# ProPrj___2025-05-21.net
KiCad netlist of a schematic drawn in EasyEDA Pro
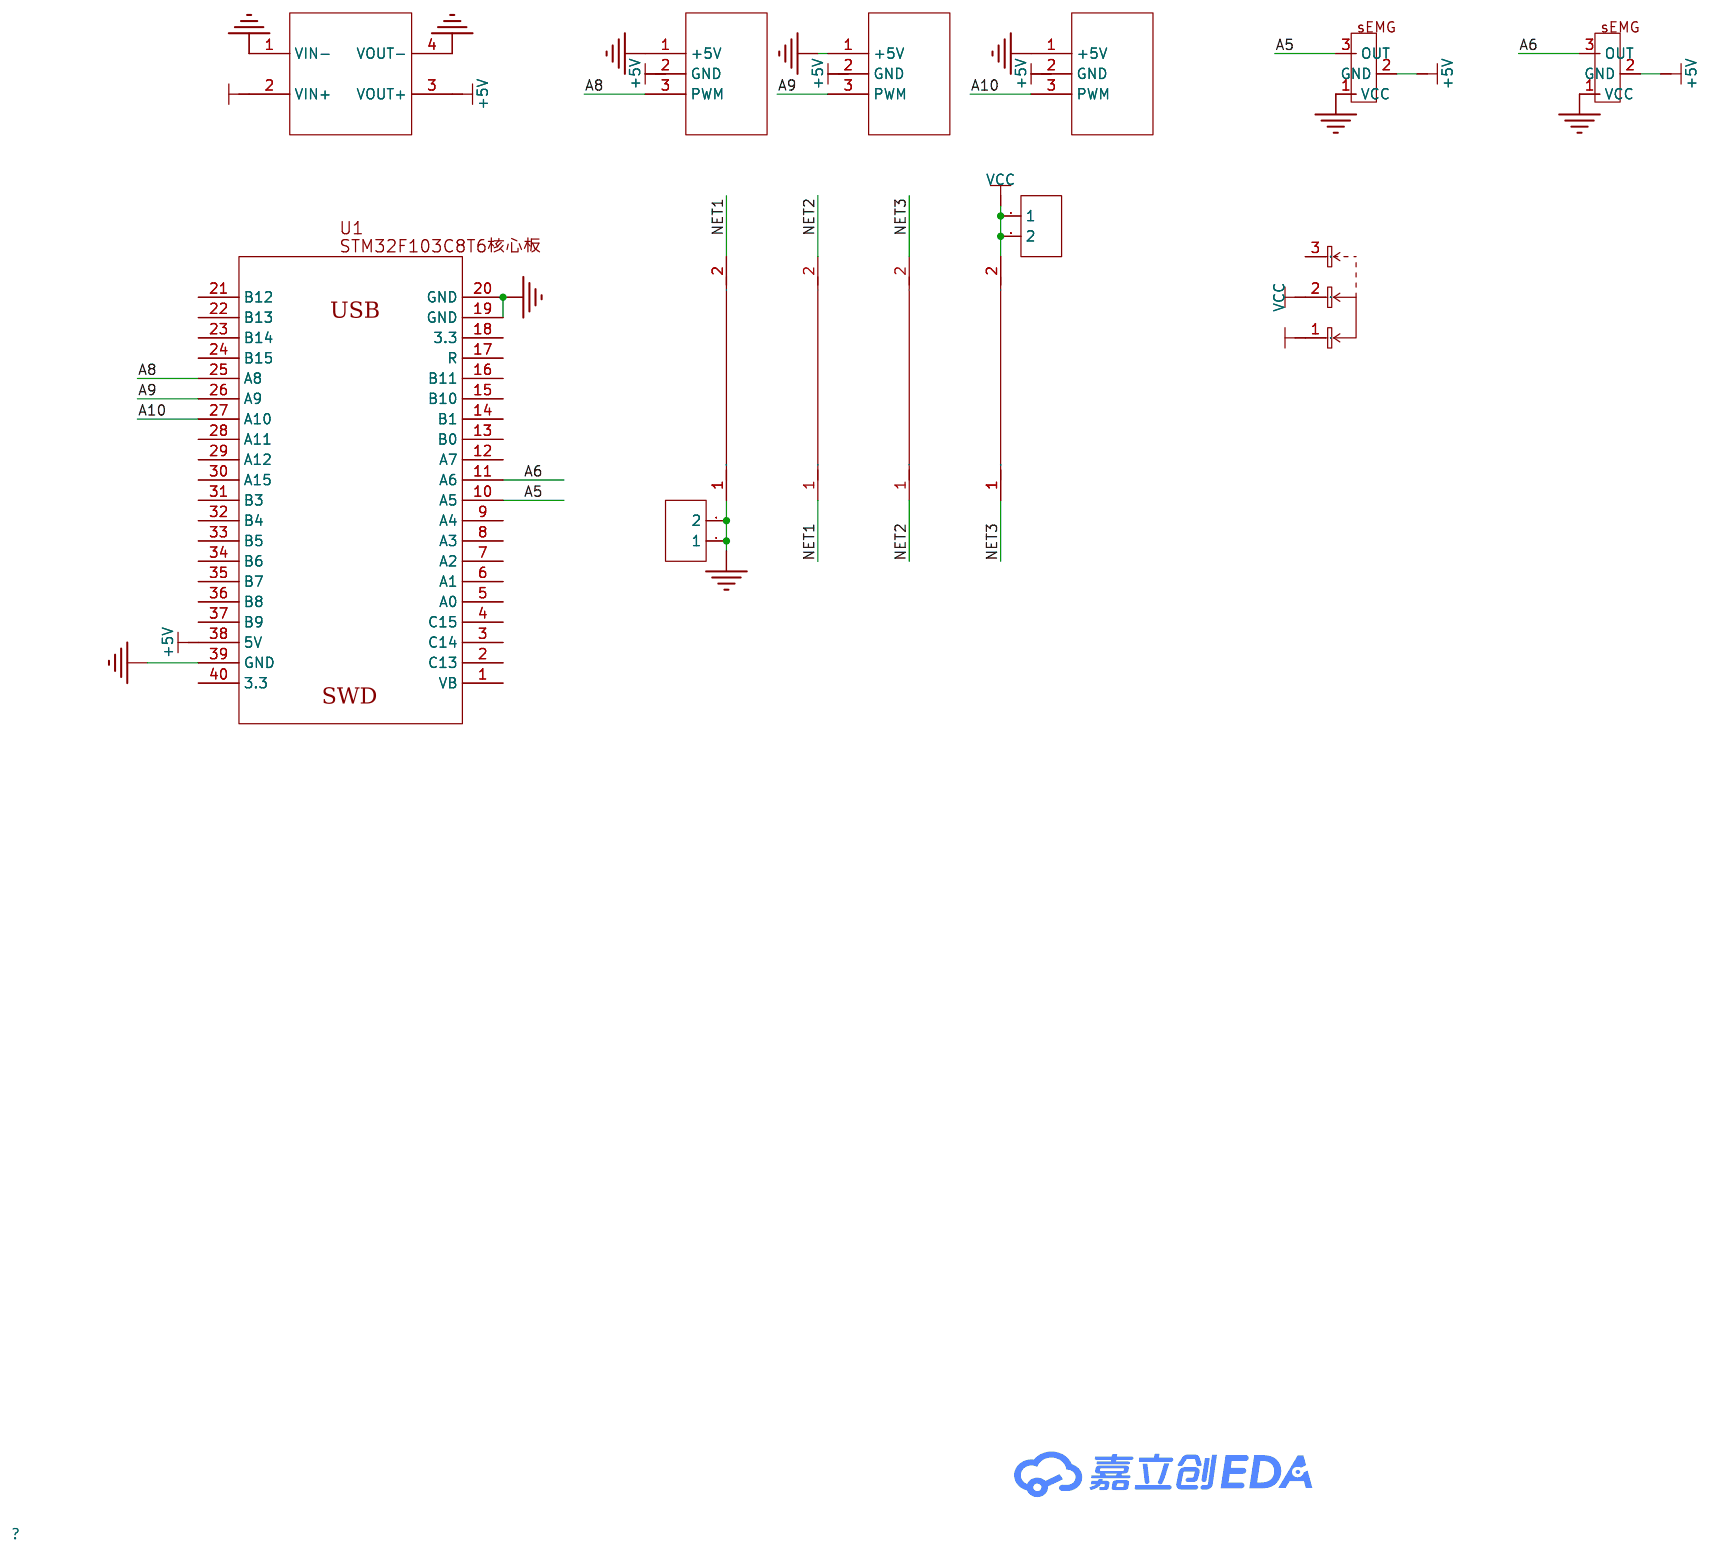
[diagram p0: schematic sheet]

(export (version "E")
  (design (tool "Eeschema 10.0.6"))
  (components
    (comp (ref "H1")
      (value "~")
      (footprint "easyedapro:HDR-TH_2P-P2.54-V-F")
      (libsource (lib "easyedapro") (part "Header-Female-2.54_1x2"))
    )
    (comp (ref "H2")
      (value "~")
      (footprint "easyedapro:HDR-TH_2P-P2.54-V-F")
      (libsource (lib "easyedapro") (part "Header-Female-2.54_1x2"))
    )
    (comp (ref "SW1")
      (value "SS-12D06L5")
      (footprint "easyedapro:SW-TH_3P-P4.70_L11.1-W12.7")
      (description "电路结构:单刀双掷;安装方式:侧插;开关颜色:黑色;额定电流(DC):3A;额定电压(DC):250V;额定电流(AC):3A;额定电压(AC):250V;机械寿命:1万次;")
      (fields (field (name "Manufacturer") "XKB Connectivity(中国星坤)"))
      (libsource (lib "easyedapro") (part "SS-12D06L5"))
    )
    (comp (ref "U1")
      (value "~")
      (footprint "easyedapro:DIP-3-2.54MM")
      (libsource (lib "easyedapro") (part "sEMG"))
    )
    (comp (ref "U3")
      (value "~")
      (footprint "easyedapro:DIP-3-2.54MM")
      (libsource (lib "easyedapro") (part "sEMG"))
    )
    (comp (ref "U4") (value "~") (footprint "easyedapro:sg90") (libsource (lib "easyedapro") (part "SG90")))
    (comp (ref "U5") (value "~") (footprint "easyedapro:sg90") (libsource (lib "easyedapro") (part "SG90")))
    (comp (ref "U6") (value "~") (footprint "easyedapro:sg90") (libsource (lib "easyedapro") (part "SG90")))
    (comp (ref "U7")
      (value "~")
      (footprint "easyedapro:STM32F103C8T6核心板")
      (libsource (lib "easyedapro") (part "STM32F103核心板"))
    )
    (comp (ref "U8")
      (value "~")
      (footprint "easyedapro:MP1584EN模块_邮票孔")
      (description "MP1584END电源模块")
      (libsource (lib "easyedapro") (part "MP1584EN模块"))
    )
    (comp (ref "U10")
      (value "~")
      (footprint "easyedapro:bat-th_cr2032")
      (libsource (lib "easyedapro") (part "CR2032 (卧式焊脚)20-6*9"))
    )
    (comp (ref "U11")
      (value "~")
      (footprint "easyedapro:bat-th_cr2032")
      (libsource (lib "easyedapro") (part "CR2032 (卧式焊脚)20-6*9"))
    )
    (comp (ref "U12")
      (value "~")
      (footprint "easyedapro:bat-th_cr2032")
      (libsource (lib "easyedapro") (part "CR2032 (卧式焊脚)20-6*9"))
    )
    (comp (ref "U13")
      (value "~")
      (footprint "easyedapro:bat-th_cr2032")
      (libsource (lib "easyedapro") (part "CR2032 (卧式焊脚)20-6*9"))
    )
  )
  (nets
    (net (code "1") (name "+5V") (class "Default")
      (node (ref "U1") (pin "2") (pinfunction "GND_2") (pintype "input"))
      (node (ref "U3") (pin "2") (pinfunction "GND_2") (pintype "input"))
      (node (ref "U4") (pin "2") (pinfunction "GND_2") (pintype "input"))
      (node (ref "U5") (pin "2") (pinfunction "GND_2") (pintype "input"))
      (node (ref "U6") (pin "2") (pinfunction "GND_2") (pintype "input"))
      (node (ref "U7") (pin "38") (pinfunction "5V_38") (pintype "input"))
      (node (ref "U8") (pin "3") (pinfunction "VOUT+_3") (pintype "input"))
    )
    (net (code "2") (name "+12V") (class "Default")
      (node (ref "SW1") (pin "1") (pinfunction "1_1") (pintype "unspecified"))
      (node (ref "U8") (pin "2") (pinfunction "VIN+_2") (pintype "input"))
    )
    (net (code "3") (name "/A5") (class "Default")
      (node (ref "U3") (pin "3") (pinfunction "OUT_3") (pintype "input"))
      (node (ref "U7") (pin "10") (pinfunction "A5_10") (pintype "input"))
    )
    (net (code "4") (name "/A6") (class "Default")
      (node (ref "U1") (pin "3") (pinfunction "OUT_3") (pintype "input"))
      (node (ref "U7") (pin "11") (pinfunction "A6_11") (pintype "input"))
    )
    (net (code "5") (name "/A8") (class "Default")
      (node (ref "U4") (pin "3") (pinfunction "PWM_3") (pintype "input"))
      (node (ref "U7") (pin "25") (pinfunction "A8_25") (pintype "input"))
    )
    (net (code "6") (name "/A9") (class "Default")
      (node (ref "U5") (pin "3") (pinfunction "PWM_3") (pintype "input"))
      (node (ref "U7") (pin "26") (pinfunction "A9_26") (pintype "input"))
    )
    (net (code "7") (name "/A10") (class "Default")
      (node (ref "U6") (pin "3") (pinfunction "PWM_3") (pintype "input"))
      (node (ref "U7") (pin "27") (pinfunction "A10_27") (pintype "input"))
    )
    (net (code "8") (name "/NET1") (class "Default")
      (node (ref "U10") (pin "2") (pinfunction "-_2") (pintype "input"))
      (node (ref "U11") (pin "1") (pinfunction "+_1") (pintype "input"))
    )
    (net (code "9") (name "/NET2") (class "Default")
      (node (ref "U11") (pin "2") (pinfunction "-_2") (pintype "input"))
      (node (ref "U12") (pin "1") (pinfunction "+_1") (pintype "input"))
    )
    (net (code "10") (name "/NET3") (class "Default")
      (node (ref "U12") (pin "2") (pinfunction "-_2") (pintype "input"))
      (node (ref "U13") (pin "1") (pinfunction "+_1") (pintype "input"))
    )
    (net (code "11") (name "GND") (class "Default")
      (node (ref "H2") (pin "1") (pinfunction "1_1") (pintype "input"))
      (node (ref "H2") (pin "2") (pinfunction "2_2") (pintype "input"))
      (node (ref "U1") (pin "1") (pinfunction "VCC_1") (pintype "input"))
      (node (ref "U10") (pin "1") (pinfunction "+_1") (pintype "input"))
      (node (ref "U3") (pin "1") (pinfunction "VCC_1") (pintype "input"))
      (node (ref "U4") (pin "1") (pinfunction "+5V_1") (pintype "input"))
      (node (ref "U5") (pin "1") (pinfunction "+5V_1") (pintype "input"))
      (node (ref "U6") (pin "1") (pinfunction "+5V_1") (pintype "input"))
      (node (ref "U7") (pin "19") (pinfunction "GND_19") (pintype "input"))
      (node (ref "U7") (pin "20") (pinfunction "GND_20") (pintype "input"))
      (node (ref "U7") (pin "39") (pinfunction "GND_39") (pintype "input"))
      (node (ref "U8") (pin "1") (pinfunction "VIN-_1") (pintype "input"))
      (node (ref "U8") (pin "4") (pinfunction "VOUT-_4") (pintype "input"))
    )
    (net (code "12") (name "VCC") (class "Default")
      (node (ref "H1") (pin "1") (pinfunction "1_1") (pintype "input"))
      (node (ref "H1") (pin "2") (pinfunction "2_2") (pintype "input"))
      (node (ref "SW1") (pin "2") (pinfunction "2_2") (pintype "unspecified"))
      (node (ref "U13") (pin "2") (pinfunction "-_2") (pintype "input"))
    )
    (net (code "13") (name "unconnected-(SW1-Pad3)") (class "Default")
      (node (ref "SW1") (pin "3") (pinfunction "3_3") (pintype "unspecified"))
    )
    (net (code "14") (name "unconnected-(U7-3.3-Pad18)") (class "Default")
      (node (ref "U7") (pin "18") (pinfunction "3.3_18") (pintype "input"))
    )
    (net (code "15") (name "unconnected-(U7-3.3-Pad40)") (class "Default")
      (node (ref "U7") (pin "40") (pinfunction "3.3_40") (pintype "input"))
    )
    (net (code "16") (name "unconnected-(U7-A0-Pad5)") (class "Default")
      (node (ref "U7") (pin "5") (pinfunction "A0_5") (pintype "input"))
    )
    (net (code "17") (name "unconnected-(U7-A1-Pad6)") (class "Default")
      (node (ref "U7") (pin "6") (pinfunction "A1_6") (pintype "input"))
    )
    (net (code "18") (name "unconnected-(U7-A2-Pad7)") (class "Default")
      (node (ref "U7") (pin "7") (pinfunction "A2_7") (pintype "input"))
    )
    (net (code "19") (name "unconnected-(U7-A3-Pad8)") (class "Default")
      (node (ref "U7") (pin "8") (pinfunction "A3_8") (pintype "input"))
    )
    (net (code "20") (name "unconnected-(U7-A4-Pad9)") (class "Default")
      (node (ref "U7") (pin "9") (pinfunction "A4_9") (pintype "input"))
    )
    (net (code "21") (name "unconnected-(U7-A7-Pad12)") (class "Default")
      (node (ref "U7") (pin "12") (pinfunction "A7_12") (pintype "input"))
    )
    (net (code "22") (name "unconnected-(U7-A11-Pad28)") (class "Default")
      (node (ref "U7") (pin "28") (pinfunction "A11_28") (pintype "input"))
    )
    (net (code "23") (name "unconnected-(U7-A12-Pad29)") (class "Default")
      (node (ref "U7") (pin "29") (pinfunction "A12_29") (pintype "input"))
    )
    (net (code "24") (name "unconnected-(U7-A15-Pad30)") (class "Default")
      (node (ref "U7") (pin "30") (pinfunction "A15_30") (pintype "input"))
    )
    (net (code "25") (name "unconnected-(U7-B0-Pad13)") (class "Default")
      (node (ref "U7") (pin "13") (pinfunction "B0_13") (pintype "input"))
    )
    (net (code "26") (name "unconnected-(U7-B1-Pad14)") (class "Default")
      (node (ref "U7") (pin "14") (pinfunction "B1_14") (pintype "input"))
    )
    (net (code "27") (name "unconnected-(U7-B3-Pad31)") (class "Default")
      (node (ref "U7") (pin "31") (pinfunction "B3_31") (pintype "input"))
    )
    (net (code "28") (name "unconnected-(U7-B4-Pad32)") (class "Default")
      (node (ref "U7") (pin "32") (pinfunction "B4_32") (pintype "input"))
    )
    (net (code "29") (name "unconnected-(U7-B5-Pad33)") (class "Default")
      (node (ref "U7") (pin "33") (pinfunction "B5_33") (pintype "input"))
    )
    (net (code "30") (name "unconnected-(U7-B6-Pad34)") (class "Default")
      (node (ref "U7") (pin "34") (pinfunction "B6_34") (pintype "input"))
    )
    (net (code "31") (name "unconnected-(U7-B7-Pad35)") (class "Default")
      (node (ref "U7") (pin "35") (pinfunction "B7_35") (pintype "input"))
    )
    (net (code "32") (name "unconnected-(U7-B8-Pad36)") (class "Default")
      (node (ref "U7") (pin "36") (pinfunction "B8_36") (pintype "input"))
    )
    (net (code "33") (name "unconnected-(U7-B9-Pad37)") (class "Default")
      (node (ref "U7") (pin "37") (pinfunction "B9_37") (pintype "input"))
    )
    (net (code "34") (name "unconnected-(U7-B10-Pad15)") (class "Default")
      (node (ref "U7") (pin "15") (pinfunction "B10_15") (pintype "input"))
    )
    (net (code "35") (name "unconnected-(U7-B11-Pad16)") (class "Default")
      (node (ref "U7") (pin "16") (pinfunction "B11_16") (pintype "input"))
    )
    (net (code "36") (name "unconnected-(U7-B12-Pad21)") (class "Default")
      (node (ref "U7") (pin "21") (pinfunction "B12_21") (pintype "input"))
    )
    (net (code "37") (name "unconnected-(U7-B13-Pad22)") (class "Default")
      (node (ref "U7") (pin "22") (pinfunction "B13_22") (pintype "input"))
    )
    (net (code "38") (name "unconnected-(U7-B14-Pad23)") (class "Default")
      (node (ref "U7") (pin "23") (pinfunction "B14_23") (pintype "input"))
    )
    (net (code "39") (name "unconnected-(U7-B15-Pad24)") (class "Default")
      (node (ref "U7") (pin "24") (pinfunction "B15_24") (pintype "input"))
    )
    (net (code "40") (name "unconnected-(U7-C13-Pad2)") (class "Default")
      (node (ref "U7") (pin "2") (pinfunction "C13_2") (pintype "input"))
    )
    (net (code "41") (name "unconnected-(U7-C14-Pad3)") (class "Default")
      (node (ref "U7") (pin "3") (pinfunction "C14_3") (pintype "input"))
    )
    (net (code "42") (name "unconnected-(U7-C15-Pad4)") (class "Default")
      (node (ref "U7") (pin "4") (pinfunction "C15_4") (pintype "input"))
    )
    (net (code "43") (name "unconnected-(U7-R-Pad17)") (class "Default")
      (node (ref "U7") (pin "17") (pinfunction "R_17") (pintype "input"))
    )
    (net (code "44") (name "unconnected-(U7-VB-Pad1)") (class "Default")
      (node (ref "U7") (pin "1") (pinfunction "VB_1") (pintype "input"))
    )
  )
)
